# STM32.net
KiCad netlist of a schematic drawn in Altium Designer
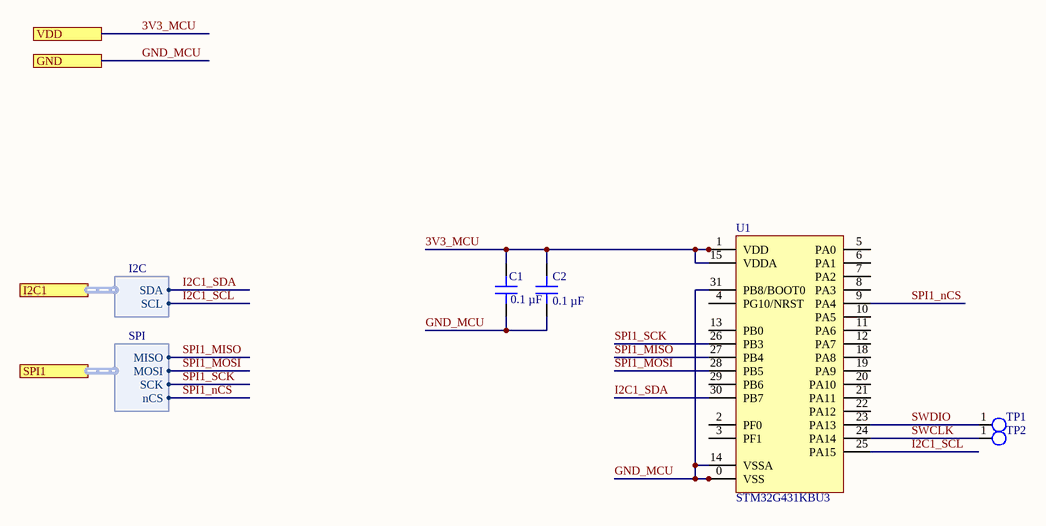
[diagram p0: STM32.SchDoc]

(export (version "E")
  (design (tool "Eeschema 10.0.6"))
  (components
    (comp (ref "C1")
      (value "0.1 µF")
      (footprint "CAP 0402_1005")
      (description "CAP CER 0.1UF 16V X7R 0402")
      (fields (field (name "PART NUMBER") "C0402C104K4RACAUTO") (field (name "MANUFACTURER") "KEMET"))
      (libsource (lib "Celestial Altium Library - altium_library") (part "Capacitor"))
    )
    (comp (ref "C2")
      (value "0.1 µF")
      (footprint "CAP 0402_1005")
      (description "CAP CER 0.1UF 16V X7R 0402")
      (fields (field (name "PART NUMBER") "C0402C104K4RACAUTO") (field (name "MANUFACTURER") "KEMET"))
      (libsource (lib "Celestial Altium Library - altium_library") (part "Capacitor"))
    )
    (comp (ref "TP1")
      (value "0.8mm")
      (footprint "TP  0.8mm")
      (description "Test point")
      (libsource (lib "IC") (part "TP 0.8mm"))
    )
    (comp (ref "TP2")
      (value "0.8mm")
      (footprint "TP  0.8mm")
      (description "Test point")
      (libsource (lib "IC") (part "TP 0.8mm"))
    )
    (comp (ref "U1")
      (value "STM32G431KBU3")
      (footprint "QFN50P400X400X60-32N")
      (description "MCU UFQFPN-32")
      (libsource (lib "IC") (part "STM32G431KBU3"))
    )
  )
  (nets
    (net (code "3") (name "/3V3_MCU") (class "Default")
      (node (ref "C1") (pin "2") (pinfunction "2_2") (pintype "passive"))
      (node (ref "C2") (pin "2") (pinfunction "2_2") (pintype "passive"))
      (node (ref "U1") (pin "1") (pinfunction "VDD_1") (pintype "passive"))
      (node (ref "U1") (pin "15") (pinfunction "VDDA_15") (pintype "passive"))
      (node (ref "U1") (pin "17") (pinfunction "VDD_17") (pintype "passive"))
    )
    (net (code "4") (name "/GND_MCU") (class "Default")
      (node (ref "C1") (pin "1") (pinfunction "1_1") (pintype "passive"))
      (node (ref "C2") (pin "1") (pinfunction "1_1") (pintype "passive"))
      (node (ref "U1") (pin "0") (pinfunction "VSS_0") (pintype "passive"))
      (node (ref "U1") (pin "14") (pinfunction "VSSA_14") (pintype "passive"))
      (node (ref "U1") (pin "16") (pinfunction "VSS_16") (pintype "passive"))
      (node (ref "U1") (pin "31") (pinfunction "PB8/BOOT0_31") (pintype "passive"))
      (node (ref "U1") (pin "32") (pinfunction "VSS_32") (pintype "passive"))
    )
    (net (code "5") (name "/I2C1_SCL") (class "Default")
      (node (ref "U1") (pin "25") (pinfunction "PA15_25") (pintype "passive"))
    )
    (net (code "6") (name "/I2C1_SDA") (class "Default")
      (node (ref "U1") (pin "30") (pinfunction "PB7_30") (pintype "passive"))
    )
    (net (code "7") (name "/SPI1_MISO") (class "Default")
      (node (ref "U1") (pin "27") (pinfunction "PB4_27") (pintype "passive"))
    )
    (net (code "8") (name "/SPI1_MOSI") (class "Default")
      (node (ref "U1") (pin "28") (pinfunction "PB5_28") (pintype "passive"))
    )
    (net (code "9") (name "/SPI1_SCK") (class "Default")
      (node (ref "U1") (pin "26") (pinfunction "PB3_26") (pintype "passive"))
    )
    (net (code "10") (name "/SPI1_nCS") (class "Default")
      (node (ref "U1") (pin "9") (pinfunction "PA4_9") (pintype "passive"))
    )
    (net (code "11") (name "/SWCLK") (class "Default")
      (node (ref "TP2") (pin "1") (pinfunction "TP_1") (pintype "passive"))
      (node (ref "U1") (pin "24") (pinfunction "PA14_24") (pintype "passive"))
    )
    (net (code "12") (name "/SWDIO") (class "Default")
      (node (ref "TP1") (pin "1") (pinfunction "TP_1") (pintype "passive"))
      (node (ref "U1") (pin "23") (pinfunction "PA13_23") (pintype "passive"))
    )
    (net (code "15") (name "unconnected-(U1-PA0-Pad5)") (class "Default")
      (node (ref "U1") (pin "5") (pinfunction "PA0_5") (pintype "passive"))
    )
    (net (code "16") (name "unconnected-(U1-PA1-Pad6)") (class "Default")
      (node (ref "U1") (pin "6") (pinfunction "PA1_6") (pintype "passive"))
    )
    (net (code "17") (name "unconnected-(U1-PA2-Pad7)") (class "Default")
      (node (ref "U1") (pin "7") (pinfunction "PA2_7") (pintype "passive"))
    )
    (net (code "18") (name "unconnected-(U1-PA3-Pad8)") (class "Default")
      (node (ref "U1") (pin "8") (pinfunction "PA3_8") (pintype "passive"))
    )
    (net (code "19") (name "unconnected-(U1-PA5-Pad10)") (class "Default")
      (node (ref "U1") (pin "10") (pinfunction "PA5_10") (pintype "passive"))
    )
    (net (code "20") (name "unconnected-(U1-PA6-Pad11)") (class "Default")
      (node (ref "U1") (pin "11") (pinfunction "PA6_11") (pintype "passive"))
    )
    (net (code "21") (name "unconnected-(U1-PA7-Pad12)") (class "Default")
      (node (ref "U1") (pin "12") (pinfunction "PA7_12") (pintype "passive"))
    )
    (net (code "22") (name "unconnected-(U1-PA8-Pad18)") (class "Default")
      (node (ref "U1") (pin "18") (pinfunction "PA8_18") (pintype "passive"))
    )
    (net (code "23") (name "unconnected-(U1-PA9-Pad19)") (class "Default")
      (node (ref "U1") (pin "19") (pinfunction "PA9_19") (pintype "passive"))
    )
    (net (code "24") (name "unconnected-(U1-PA10-Pad20)") (class "Default")
      (node (ref "U1") (pin "20") (pinfunction "PA10_20") (pintype "passive"))
    )
    (net (code "25") (name "unconnected-(U1-PA11-Pad21)") (class "Default")
      (node (ref "U1") (pin "21") (pinfunction "PA11_21") (pintype "passive"))
    )
    (net (code "26") (name "unconnected-(U1-PA12-Pad22)") (class "Default")
      (node (ref "U1") (pin "22") (pinfunction "PA12_22") (pintype "passive"))
    )
    (net (code "27") (name "unconnected-(U1-PB0-Pad13)") (class "Default")
      (node (ref "U1") (pin "13") (pinfunction "PB0_13") (pintype "passive"))
    )
    (net (code "28") (name "unconnected-(U1-PB6-Pad29)") (class "Default")
      (node (ref "U1") (pin "29") (pinfunction "PB6_29") (pintype "passive"))
    )
    (net (code "29") (name "unconnected-(U1-PF0-Pad2)") (class "Default")
      (node (ref "U1") (pin "2") (pinfunction "PF0_2") (pintype "passive"))
    )
    (net (code "30") (name "unconnected-(U1-PF1-Pad3)") (class "Default")
      (node (ref "U1") (pin "3") (pinfunction "PF1_3") (pintype "passive"))
    )
    (net (code "31") (name "unconnected-(U1-PG10{slash}NRST-Pad4)") (class "Default")
      (node (ref "U1") (pin "4") (pinfunction "PG10/NRST_4") (pintype "passive"))
    )
  )
)
